# Sheet2.net
KiCad netlist of a schematic drawn in Altium Designer
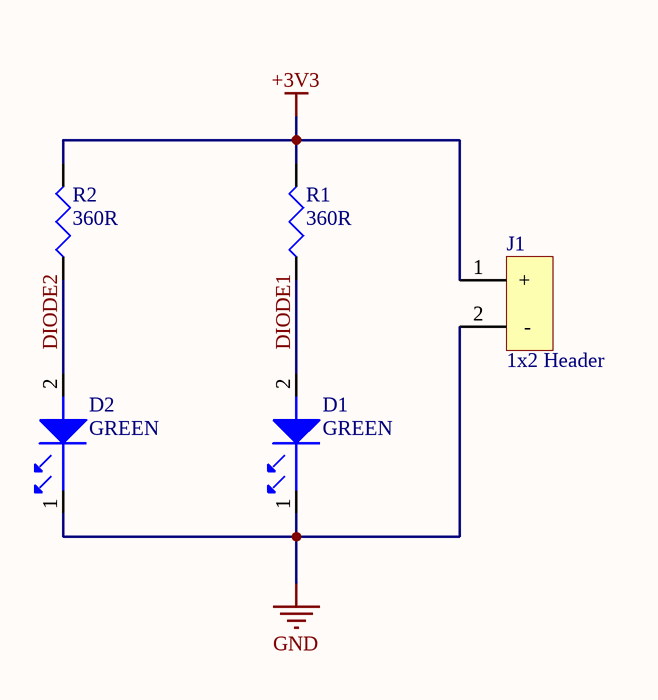
[diagram p0: Sheet2.SchDoc]

(export (version "E")
  (design (tool "Eeschema 10.0.6"))
  (components
    (comp (ref "D1")
      (value "GREEN")
      (footprint "LED0603G")
      (description "LED GREEN ESS II SMD")
      (fields
        (field (name "MANUFACTURER") "Panasonic SSG")
        (field (name "MANUFACTURER PART NUMBER") "LNJ337W83RA")
      )
      (libsource (lib "Schlib1") (part "LNJ337W83RA"))
    )
    (comp (ref "D2")
      (value "GREEN")
      (footprint "LED0603G")
      (description "LED GREEN ESS II SMD")
      (fields
        (field (name "MANUFACTURER") "Panasonic SSG")
        (field (name "MANUFACTURER PART NUMBER") "LNJ337W83RA")
      )
      (libsource (lib "Schlib1") (part "LNJ337W83RA"))
    )
    (comp (ref "J1")
      (value "1x2 Header")
      (footprint "HDR1X2")
      (description "Conn Wire to Board HDR 2 POS 2.54mm Solder ST Thru-Hole Bag")
      (fields (field (name "MANUFACTURER") "Molex") (field (name "MANUFACTURER PART NUMBER") "22-29-2021"))
      (libsource (lib "Schlib1") (part "22-29-2021 (2)"))
    )
    (comp (ref "R1")
      (value "360R")
      (footprint "R0805")
      (description "Res Thick Film 0805 360 Ohm 1% 0.125W(1/8W) ±100ppm/C Molded SMD Automotive Paper T/R")
      (fields
        (field (name "MANUFACTURER") "Vishay")
        (field (name "MANUFACTURER PART NUMBER") "CRCW0805360RFKEA")
      )
      (libsource (lib "Schlib1") (part "CRCW0805360RFKEA (2)"))
    )
    (comp (ref "R2")
      (value "360R")
      (footprint "R0805")
      (description "Res Thick Film 0805 360 Ohm 1% 0.125W(1/8W) ±100ppm/C Molded SMD Automotive Paper T/R")
      (fields
        (field (name "MANUFACTURER") "Vishay")
        (field (name "MANUFACTURER PART NUMBER") "CRCW0805360RFKEA")
      )
      (libsource (lib "Schlib1") (part "CRCW0805360RFKEA (2)"))
    )
  )
  (nets
    (net (code "1") (name "+3V3") (class "Default")
      (node (ref "J1") (pin "1") (pinfunction "+_1") (pintype "passive"))
      (node (ref "R1") (pin "2") (pinfunction "2_2") (pintype "passive"))
      (node (ref "R2") (pin "2") (pinfunction "2_2") (pintype "passive"))
    )
    (net (code "2") (name "/DIODE1") (class "Default")
      (node (ref "D1") (pin "2") (pinfunction "2_2") (pintype "passive"))
      (node (ref "R1") (pin "1") (pinfunction "1_1") (pintype "passive"))
    )
    (net (code "3") (name "/DIODE2") (class "Default")
      (node (ref "D2") (pin "2") (pinfunction "2_2") (pintype "passive"))
      (node (ref "R2") (pin "1") (pinfunction "1_1") (pintype "passive"))
    )
    (net (code "4") (name "GND") (class "Default")
      (node (ref "D1") (pin "1") (pinfunction "1_1") (pintype "passive"))
      (node (ref "D2") (pin "1") (pinfunction "1_1") (pintype "passive"))
      (node (ref "J1") (pin "2") (pinfunction "_-_2") (pintype "passive"))
    )
  )
)
